# TMC2130.net
KiCad netlist of a schematic drawn in Altium Designer
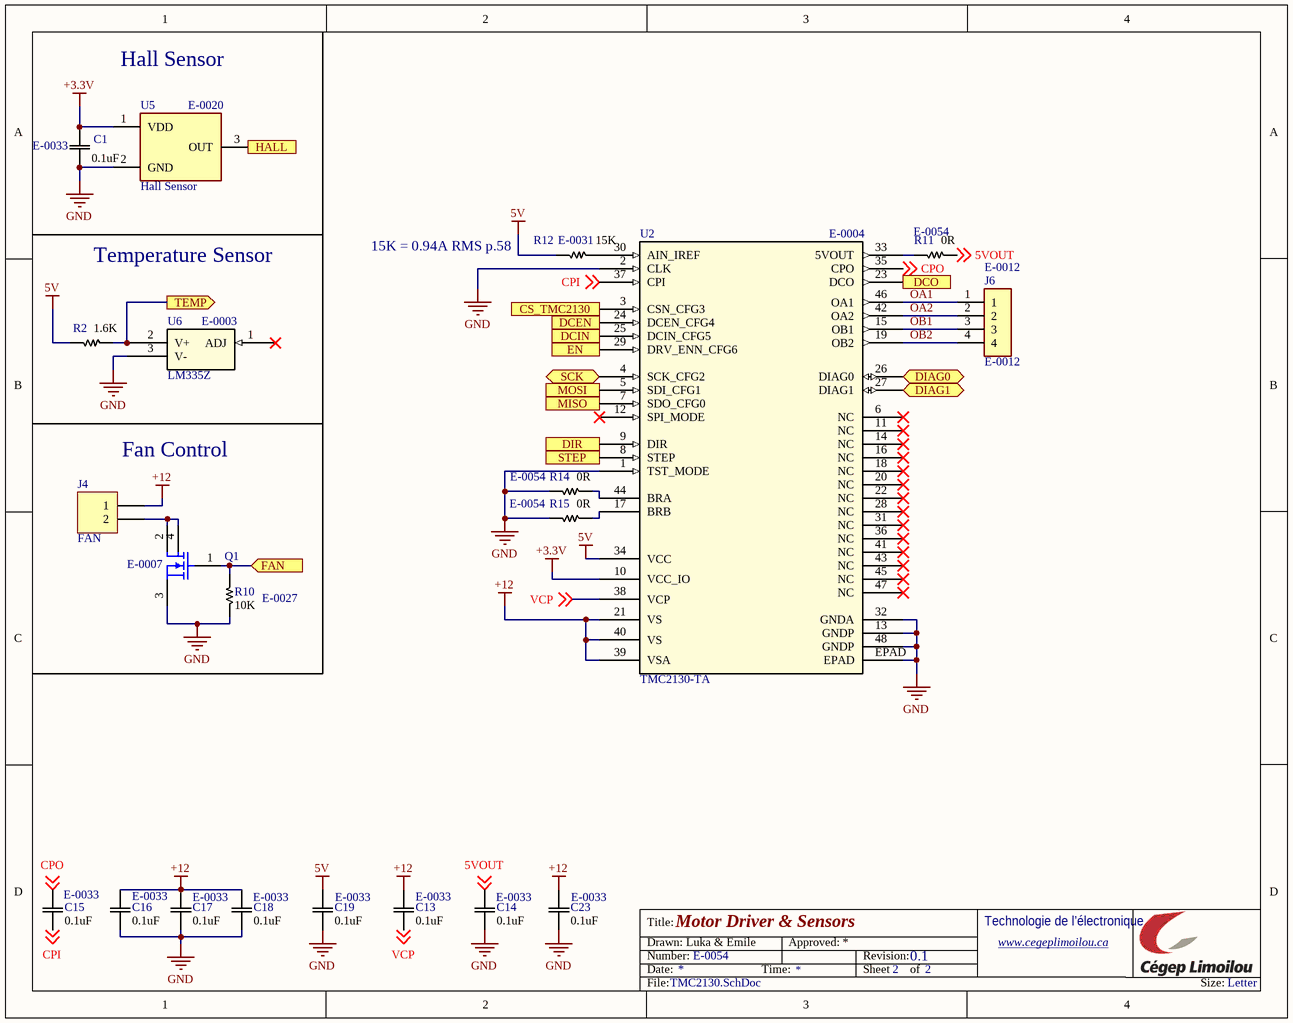
[diagram p0: TMC2130.SchDoc]

(export (version "E")
  (design (tool "Eeschema 10.0.6"))
  (components
    (comp (ref "C1")
      (value "0.1uF")
      (footprint "0603")
      (description "0.1uF Capacitor 0603 SMD")
      (fields
        (field (name "MANUFACTURER_PART_NUMBER") "C0603C104Z3VACTU")
        (field (name "EXCEL NUMBER") "E-0033")
        (field (name "Comment") "E-0033")
        (field (name "COPYRIGHT") "Luka & Émile")
      )
      (libsource (lib "Motor Driver") (part "E-0033"))
    )
    (comp (ref "C13")
      (value "0.1uF")
      (footprint "0603")
      (description "0.1uF Capacitor 0603 SMD")
      (fields
        (field (name "MANUFACTURER_PART_NUMBER") "C0603C104Z3VACTU")
        (field (name "EXCEL NUMBER") "E-0033")
        (field (name "Comment") "E-0033")
        (field (name "COPYRIGHT") "Luka & Émile")
      )
      (libsource (lib "Motor Driver") (part "E-0033"))
    )
    (comp (ref "C14")
      (value "0.1uF")
      (footprint "0603")
      (description "0.1uF Capacitor 0603 SMD")
      (fields
        (field (name "MANUFACTURER_PART_NUMBER") "C0603C104Z3VACTU")
        (field (name "EXCEL NUMBER") "E-0033")
        (field (name "Comment") "E-0033")
        (field (name "COPYRIGHT") "Luka & Émile")
      )
      (libsource (lib "Motor Driver") (part "E-0033"))
    )
    (comp (ref "C15")
      (value "0.1uF")
      (footprint "0603")
      (description "0.1uF Capacitor 0603 SMD")
      (fields
        (field (name "MANUFACTURER_PART_NUMBER") "C0603C104Z3VACTU")
        (field (name "EXCEL NUMBER") "E-0033")
        (field (name "Comment") "E-0033")
        (field (name "COPYRIGHT") "Luka & Émile")
      )
      (libsource (lib "Motor Driver") (part "E-0033"))
    )
    (comp (ref "C16")
      (value "0.1uF")
      (footprint "0603")
      (description "0.1uF Capacitor 0603 SMD")
      (fields
        (field (name "MANUFACTURER_PART_NUMBER") "C0603C104Z3VACTU")
        (field (name "EXCEL NUMBER") "E-0033")
        (field (name "Comment") "E-0033")
        (field (name "COPYRIGHT") "Luka & Émile")
      )
      (libsource (lib "Motor Driver") (part "E-0033"))
    )
    (comp (ref "C17")
      (value "0.1uF")
      (footprint "0603")
      (description "0.1uF Capacitor 0603 SMD")
      (fields
        (field (name "MANUFACTURER_PART_NUMBER") "C0603C104Z3VACTU")
        (field (name "EXCEL NUMBER") "E-0033")
        (field (name "Comment") "E-0033")
        (field (name "COPYRIGHT") "Luka & Émile")
      )
      (libsource (lib "Motor Driver") (part "E-0033"))
    )
    (comp (ref "C18")
      (value "0.1uF")
      (footprint "0603")
      (description "0.1uF Capacitor 0603 SMD")
      (fields
        (field (name "MANUFACTURER_PART_NUMBER") "C0603C104Z3VACTU")
        (field (name "EXCEL NUMBER") "E-0033")
        (field (name "Comment") "E-0033")
        (field (name "COPYRIGHT") "Luka & Émile")
      )
      (libsource (lib "Motor Driver") (part "E-0033"))
    )
    (comp (ref "C19")
      (value "0.1uF")
      (footprint "0603")
      (description "0.1uF Capacitor 0603 SMD")
      (fields
        (field (name "MANUFACTURER_PART_NUMBER") "C0603C104Z3VACTU")
        (field (name "EXCEL NUMBER") "E-0033")
        (field (name "Comment") "E-0033")
        (field (name "COPYRIGHT") "Luka & Émile")
      )
      (libsource (lib "Motor Driver") (part "E-0033"))
    )
    (comp (ref "C23")
      (value "0.1uF")
      (footprint "0603")
      (description "0.1uF Capacitor 0603 SMD")
      (fields
        (field (name "MANUFACTURER_PART_NUMBER") "C0603C104Z3VACTU")
        (field (name "EXCEL NUMBER") "E-0033")
        (field (name "Comment") "E-0033")
        (field (name "COPYRIGHT") "Luka & Émile")
      )
      (libsource (lib "Motor Driver") (part "E-0033"))
    )
    (comp (ref "J4")
      (value "FAN")
      (footprint "HDR1X2")
      (description "Header, 2-Pin")
      (fields
        (field (name "MANUFACTURER_PART_NUMBER") "61300411121")
        (field (name "COPYRIGHT") "Luka & Émile")
      )
      (libsource (lib "Motor Driver") (part "E-0047"))
    )
    (comp (ref "J6")
      (value "E-0012")
      (footprint "JST 4POS 2.5mm 90°")
      (description "Connector JST 4POS")
      (fields
        (field (name "MANUFACTURER_PART_NUMBER") "S4B-XH-A(LF)(SN)")
        (field (name "EXCEL NUMBER") "E-0012")
        (field (name "COPYRIGHT") "Luka & Émile")
      )
      (libsource (lib "Motor Driver") (part "E-0012"))
    )
    (comp (ref "Q1")
      (value "E-0007")
      (footprint "SOT223_M")
      (description "55V 7A SOT223")
      (fields
        (field (name "EXCEL NUMBER") "E-0007")
        (field (name "MANUFACTURER_PART_NUMBER") "BUK9880-55A/CUX")
        (field (name "COPYRIGHT") "Luka & Émile")
      )
      (libsource (lib "Motor Driver") (part "E-0007"))
    )
    (comp (ref "R2")
      (value "1.6K")
      (footprint "0603")
      (description "1.6K Resistor 0603 SMD")
      (fields
        (field (name "MANUFACTURER_PART_NUMBER") "CRCW06031K60JNEA")
        (field (name "Comment") "E-0050")
        (field (name "COPYRIGHT") "Luka & Émile")
      )
      (libsource (lib "Motor Driver") (part "E-0050"))
    )
    (comp (ref "R10")
      (value "10K")
      (footprint "0603")
      (description "10K Resistor 0603 SMD")
      (fields
        (field (name "MANUFACTURER_PART_NUMBER") "RMCF0603JT10K0")
        (field (name "EXCEL NUMBER") "E-0027")
        (field (name "Comment") "Resistor 0603")
        (field (name "COPYRIGHT") "Luka & Émile")
      )
      (libsource (lib "Motor Driver") (part "E-0027"))
    )
    (comp (ref "R11")
      (value "0R")
      (footprint "0603")
      (description "0R Resistor 0603 SMD")
      (fields
        (field (name "EXCEL NUMBER") "E-0054")
        (field (name "Comment") "Resistor 0603")
        (field (name "COPYRIGHT") "Luka & Émile")
      )
      (libsource (lib "Motor Driver") (part "E-0056"))
    )
    (comp (ref "R12")
      (value "15K")
      (footprint "0603")
      (description "15K Resistor 0603 SMD")
      (fields
        (field (name "MANUFACTURER_PART_NUMBER") "RMCF0603FG15K0")
        (field (name "EXCEL NUMBER") "E-0031")
        (field (name "Comment") "E-0031")
        (field (name "COPYRIGHT") "Luka & Émile")
      )
      (libsource (lib "Motor Driver") (part "E-0031"))
    )
    (comp (ref "R14")
      (value "0R")
      (footprint "0603")
      (description "0R Resistor 0603 SMD")
      (fields
        (field (name "EXCEL NUMBER") "E-0054")
        (field (name "Comment") "Resistor 0603")
        (field (name "COPYRIGHT") "Luka & Émile")
      )
      (libsource (lib "Motor Driver") (part "E-0056"))
    )
    (comp (ref "R15")
      (value "0R")
      (footprint "0603")
      (description "0R Resistor 0603 SMD")
      (fields
        (field (name "EXCEL NUMBER") "E-0054")
        (field (name "Comment") "Resistor 0603")
        (field (name "COPYRIGHT") "Luka & Émile")
      )
      (libsource (lib "Motor Driver") (part "E-0056"))
    )
    (comp (ref "U2")
      (value "TMC2130-TA")
      (footprint "eTQFP48_9x9")
      (description "Motor Driver TMC2130-TA")
      (fields
        (field (name "MANUFACTURER_PART_NUMBER") "TMC2130-TA-T")
        (field (name "EXCEL NUMBER") "E-0004")
        (field (name "COPYRIGHT") "Luka & Émile")
      )
      (libsource (lib "Motor Driver") (part "E-0004"))
    )
    (comp (ref "U5")
      (value "Hall Sensor")
      (footprint "Footprint_Emile:AH372PB")
      (fields
        (field (name "MANUFACTURER_PART_NUMBER") "AH372-P-B")
        (field (name "EXCEL NUMBER") "E-0020")
        (field (name "COPYRIGHT") "Luka & Émile")
      )
      (libsource (lib "Motor Driver") (part "E-0020"))
    )
    (comp (ref "U6")
      (value "LM335Z")
      (footprint "TO92")
      (description "Temperature Sensor LM335Z")
      (fields (field (name "EXCEL NUMBER") "E-0003") (field (name "COPYRIGHT") "Luka & Émile"))
      (libsource (lib "Motor Driver") (part "E-0003"))
    )
  )
  (nets
    (net (code "1") (name "+3.3V") (class "Default")
      (node (ref "C1") (pin "2") (pinfunction "2_2") (pintype "passive"))
      (node (ref "U2") (pin "10") (pinfunction "VCC_IO_10") (pintype "power_in"))
      (node (ref "U5") (pin "1") (pinfunction "VDD_1") (pintype "passive"))
    )
    (net (code "2") (name "+12") (class "Default")
      (node (ref "C13") (pin "2") (pinfunction "2_2") (pintype "passive"))
      (node (ref "C16") (pin "2") (pinfunction "2_2") (pintype "passive"))
      (node (ref "C17") (pin "2") (pinfunction "2_2") (pintype "passive"))
      (node (ref "C18") (pin "2") (pinfunction "2_2") (pintype "passive"))
      (node (ref "C23") (pin "2") (pinfunction "2_2") (pintype "passive"))
      (node (ref "J4") (pin "1") (pinfunction "1_1") (pintype "passive"))
      (node (ref "U2") (pin "21") (pinfunction "VS_21") (pintype "power_in"))
      (node (ref "U2") (pin "39") (pinfunction "VSA_39") (pintype "power_in"))
      (node (ref "U2") (pin "40") (pinfunction "VS_40") (pintype "power_in"))
    )
    (net (code "3") (name "/CS_TMC2130") (class "Default")
      (node (ref "U2") (pin "3") (pinfunction "CSN_CFG3_3") (pintype "input"))
    )
    (net (code "4") (name "/DCEN") (class "Default")
      (node (ref "U2") (pin "24") (pinfunction "DCEN_CFG4_24") (pintype "input"))
    )
    (net (code "5") (name "/DCIN") (class "Default")
      (node (ref "U2") (pin "25") (pinfunction "DCIN_CFG5_25") (pintype "input"))
    )
    (net (code "6") (name "/DCO") (class "Default")
      (node (ref "U2") (pin "23") (pinfunction "DCO_23") (pintype "output"))
    )
    (net (code "7") (name "/DIAG0") (class "Default")
      (node (ref "U2") (pin "26") (pinfunction "DIAG0_26") (pintype "bidirectional"))
    )
    (net (code "8") (name "/DIAG1") (class "Default")
      (node (ref "U2") (pin "27") (pinfunction "DIAG1_27") (pintype "bidirectional"))
    )
    (net (code "9") (name "/DIR") (class "Default")
      (node (ref "U2") (pin "9") (pinfunction "DIR_9") (pintype "input"))
    )
    (net (code "10") (name "/EN") (class "Default")
      (node (ref "U2") (pin "29") (pinfunction "DRV_ENN_CFG6_29") (pintype "input"))
    )
    (net (code "11") (name "/FAN") (class "Default")
      (node (ref "Q1") (pin "1") (pinfunction "G_1") (pintype "passive"))
      (node (ref "R10") (pin "2") (pinfunction "2_2") (pintype "passive"))
    )
    (net (code "12") (name "/HALL") (class "Default")
      (node (ref "U5") (pin "3") (pinfunction "OUT_3") (pintype "passive"))
    )
    (net (code "13") (name "/MISO") (class "Default")
      (node (ref "U2") (pin "7") (pinfunction "SDO_CFG0_7") (pintype "input"))
    )
    (net (code "14") (name "/MOSI") (class "Default")
      (node (ref "U2") (pin "5") (pinfunction "SDI_CFG1_5") (pintype "input"))
    )
    (net (code "15") (name "/OA1") (class "Default")
      (node (ref "J6") (pin "1") (pinfunction "1_1") (pintype "passive"))
      (node (ref "U2") (pin "46") (pinfunction "OA1_46") (pintype "output"))
    )
    (net (code "16") (name "/OA2") (class "Default")
      (node (ref "J6") (pin "2") (pinfunction "2_2") (pintype "passive"))
      (node (ref "U2") (pin "42") (pinfunction "OA2_42") (pintype "output"))
    )
    (net (code "17") (name "/OB1") (class "Default")
      (node (ref "J6") (pin "3") (pinfunction "3_3") (pintype "passive"))
      (node (ref "U2") (pin "15") (pinfunction "OB1_15") (pintype "output"))
    )
    (net (code "18") (name "/OB2") (class "Default")
      (node (ref "J6") (pin "4") (pinfunction "4_4") (pintype "passive"))
      (node (ref "U2") (pin "19") (pinfunction "OB2_19") (pintype "output"))
    )
    (net (code "19") (name "/SCK") (class "Default")
      (node (ref "U2") (pin "4") (pinfunction "SCK_CFG2_4") (pintype "input"))
    )
    (net (code "20") (name "/STEP") (class "Default")
      (node (ref "U2") (pin "8") (pinfunction "STEP_8") (pintype "input"))
    )
    (net (code "21") (name "/TEMP") (class "Default")
      (node (ref "R2") (pin "2") (pinfunction "2_2") (pintype "passive"))
      (node (ref "U6") (pin "2") (pinfunction "V+_2") (pintype "power_in"))
    )
    (net (code "22") (name "5V") (class "Default")
      (node (ref "C19") (pin "2") (pinfunction "2_2") (pintype "passive"))
      (node (ref "R12") (pin "1") (pinfunction "1_1") (pintype "passive"))
      (node (ref "R2") (pin "1") (pinfunction "1_1") (pintype "passive"))
      (node (ref "U2") (pin "34") (pinfunction "VCC_34") (pintype "power_in"))
    )
    (net (code "23") (name "5VOUT") (class "Default")
      (node (ref "C14") (pin "2") (pinfunction "2_2") (pintype "passive"))
      (node (ref "R11") (pin "2") (pinfunction "2_2") (pintype "passive"))
    )
    (net (code "24") (name "CPI") (class "Default")
      (node (ref "C15") (pin "1") (pinfunction "1_1") (pintype "passive"))
      (node (ref "U2") (pin "37") (pinfunction "CPI_37") (pintype "input"))
    )
    (net (code "25") (name "CPO") (class "Default")
      (node (ref "C15") (pin "2") (pinfunction "2_2") (pintype "passive"))
      (node (ref "U2") (pin "35") (pinfunction "CPO_35") (pintype "output"))
    )
    (net (code "26") (name "GND") (class "Default")
      (node (ref "C1") (pin "1") (pinfunction "1_1") (pintype "passive"))
      (node (ref "C14") (pin "1") (pinfunction "1_1") (pintype "passive"))
      (node (ref "C16") (pin "1") (pinfunction "1_1") (pintype "passive"))
      (node (ref "C17") (pin "1") (pinfunction "1_1") (pintype "passive"))
      (node (ref "C18") (pin "1") (pinfunction "1_1") (pintype "passive"))
      (node (ref "C19") (pin "1") (pinfunction "1_1") (pintype "passive"))
      (node (ref "C23") (pin "1") (pinfunction "1_1") (pintype "passive"))
      (node (ref "Q1") (pin "3") (pinfunction "S_3") (pintype "passive"))
      (node (ref "R10") (pin "1") (pinfunction "1_1") (pintype "passive"))
      (node (ref "R14") (pin "1") (pinfunction "1_1") (pintype "passive"))
      (node (ref "R15") (pin "1") (pinfunction "1_1") (pintype "passive"))
      (node (ref "U2") (pin "1") (pinfunction "TST_MODE_1") (pintype "input"))
      (node (ref "U2") (pin "13") (pinfunction "GNDP_13") (pintype "power_in"))
      (node (ref "U2") (pin "2") (pinfunction "CLK_2") (pintype "input"))
      (node (ref "U2") (pin "32") (pinfunction "GNDA_32") (pintype "power_in"))
      (node (ref "U2") (pin "48") (pinfunction "GNDP_48") (pintype "power_in"))
      (node (ref "U2") (pin "EPAD") (pinfunction "EPAD_EPAD") (pintype "passive"))
      (node (ref "U5") (pin "2") (pinfunction "GND_2") (pintype "passive"))
      (node (ref "U6") (pin "3") (pinfunction "V-_3") (pintype "power_in"))
    )
    (net (code "27") (name "Net-(J4-Pad2)") (class "Default")
      (node (ref "J4") (pin "2") (pinfunction "2_2") (pintype "passive"))
      (node (ref "Q1") (pin "2") (pinfunction "D_2") (pintype "passive"))
      (node (ref "Q1") (pin "4") (pinfunction "D_4") (pintype "passive"))
    )
    (net (code "28") (name "Net-(U2-5VOUT)") (class "Default")
      (node (ref "R11") (pin "1") (pinfunction "1_1") (pintype "passive"))
      (node (ref "U2") (pin "33") (pinfunction "5VOUT_33") (pintype "output"))
    )
    (net (code "29") (name "Net-(U2-AIN_IREF)") (class "Default")
      (node (ref "R12") (pin "2") (pinfunction "2_2") (pintype "passive"))
      (node (ref "U2") (pin "30") (pinfunction "AIN_IREF_30") (pintype "input"))
    )
    (net (code "30") (name "Net-(U2-BRA)") (class "Default")
      (node (ref "R14") (pin "2") (pinfunction "2_2") (pintype "passive"))
      (node (ref "U2") (pin "44") (pinfunction "BRA_44") (pintype "passive"))
    )
    (net (code "31") (name "Net-(U2-BRB)") (class "Default")
      (node (ref "R15") (pin "2") (pinfunction "2_2") (pintype "passive"))
      (node (ref "U2") (pin "17") (pinfunction "BRB_17") (pintype "passive"))
    )
    (net (code "32") (name "VCP") (class "Default")
      (node (ref "C13") (pin "1") (pinfunction "1_1") (pintype "passive"))
      (node (ref "U2") (pin "38") (pinfunction "VCP_38") (pintype "power_in"))
    )
    (net (code "33") (name "unconnected-(U2-NC-Pad6)") (class "Default")
      (node (ref "U2") (pin "6") (pinfunction "NC_6") (pintype "passive+no_connect"))
    )
    (net (code "34") (name "unconnected-(U2-NC-Pad11)") (class "Default")
      (node (ref "U2") (pin "11") (pinfunction "NC_11") (pintype "passive+no_connect"))
    )
    (net (code "35") (name "unconnected-(U2-NC-Pad14)") (class "Default")
      (node (ref "U2") (pin "14") (pinfunction "NC_14") (pintype "passive+no_connect"))
    )
    (net (code "36") (name "unconnected-(U2-NC-Pad16)") (class "Default")
      (node (ref "U2") (pin "16") (pinfunction "NC_16") (pintype "passive+no_connect"))
    )
    (net (code "37") (name "unconnected-(U2-NC-Pad18)") (class "Default")
      (node (ref "U2") (pin "18") (pinfunction "NC_18") (pintype "passive+no_connect"))
    )
    (net (code "38") (name "unconnected-(U2-NC-Pad20)") (class "Default")
      (node (ref "U2") (pin "20") (pinfunction "NC_20") (pintype "passive+no_connect"))
    )
    (net (code "39") (name "unconnected-(U2-NC-Pad22)") (class "Default")
      (node (ref "U2") (pin "22") (pinfunction "NC_22") (pintype "passive+no_connect"))
    )
    (net (code "40") (name "unconnected-(U2-NC-Pad28)") (class "Default")
      (node (ref "U2") (pin "28") (pinfunction "NC_28") (pintype "passive+no_connect"))
    )
    (net (code "41") (name "unconnected-(U2-NC-Pad31)") (class "Default")
      (node (ref "U2") (pin "31") (pinfunction "NC_31") (pintype "passive+no_connect"))
    )
    (net (code "42") (name "unconnected-(U2-NC-Pad36)") (class "Default")
      (node (ref "U2") (pin "36") (pinfunction "NC_36") (pintype "passive+no_connect"))
    )
    (net (code "43") (name "unconnected-(U2-NC-Pad41)") (class "Default")
      (node (ref "U2") (pin "41") (pinfunction "NC_41") (pintype "passive+no_connect"))
    )
    (net (code "44") (name "unconnected-(U2-NC-Pad43)") (class "Default")
      (node (ref "U2") (pin "43") (pinfunction "NC_43") (pintype "passive+no_connect"))
    )
    (net (code "45") (name "unconnected-(U2-NC-Pad45)") (class "Default")
      (node (ref "U2") (pin "45") (pinfunction "NC_45") (pintype "passive+no_connect"))
    )
    (net (code "46") (name "unconnected-(U2-NC-Pad47)") (class "Default")
      (node (ref "U2") (pin "47") (pinfunction "NC_47") (pintype "passive+no_connect"))
    )
    (net (code "47") (name "unconnected-(U2-SPI_MODE-Pad12)") (class "Default")
      (node (ref "U2") (pin "12") (pinfunction "SPI_MODE_12") (pintype "input+no_connect"))
    )
    (net (code "48") (name "unconnected-(U6-ADJ-Pad1)") (class "Default")
      (node (ref "U6") (pin "1") (pinfunction "ADJ_1") (pintype "input+no_connect"))
    )
  )
)
